# SOC_Power_Pins.net
KiCad netlist of a schematic drawn in Altium Designer
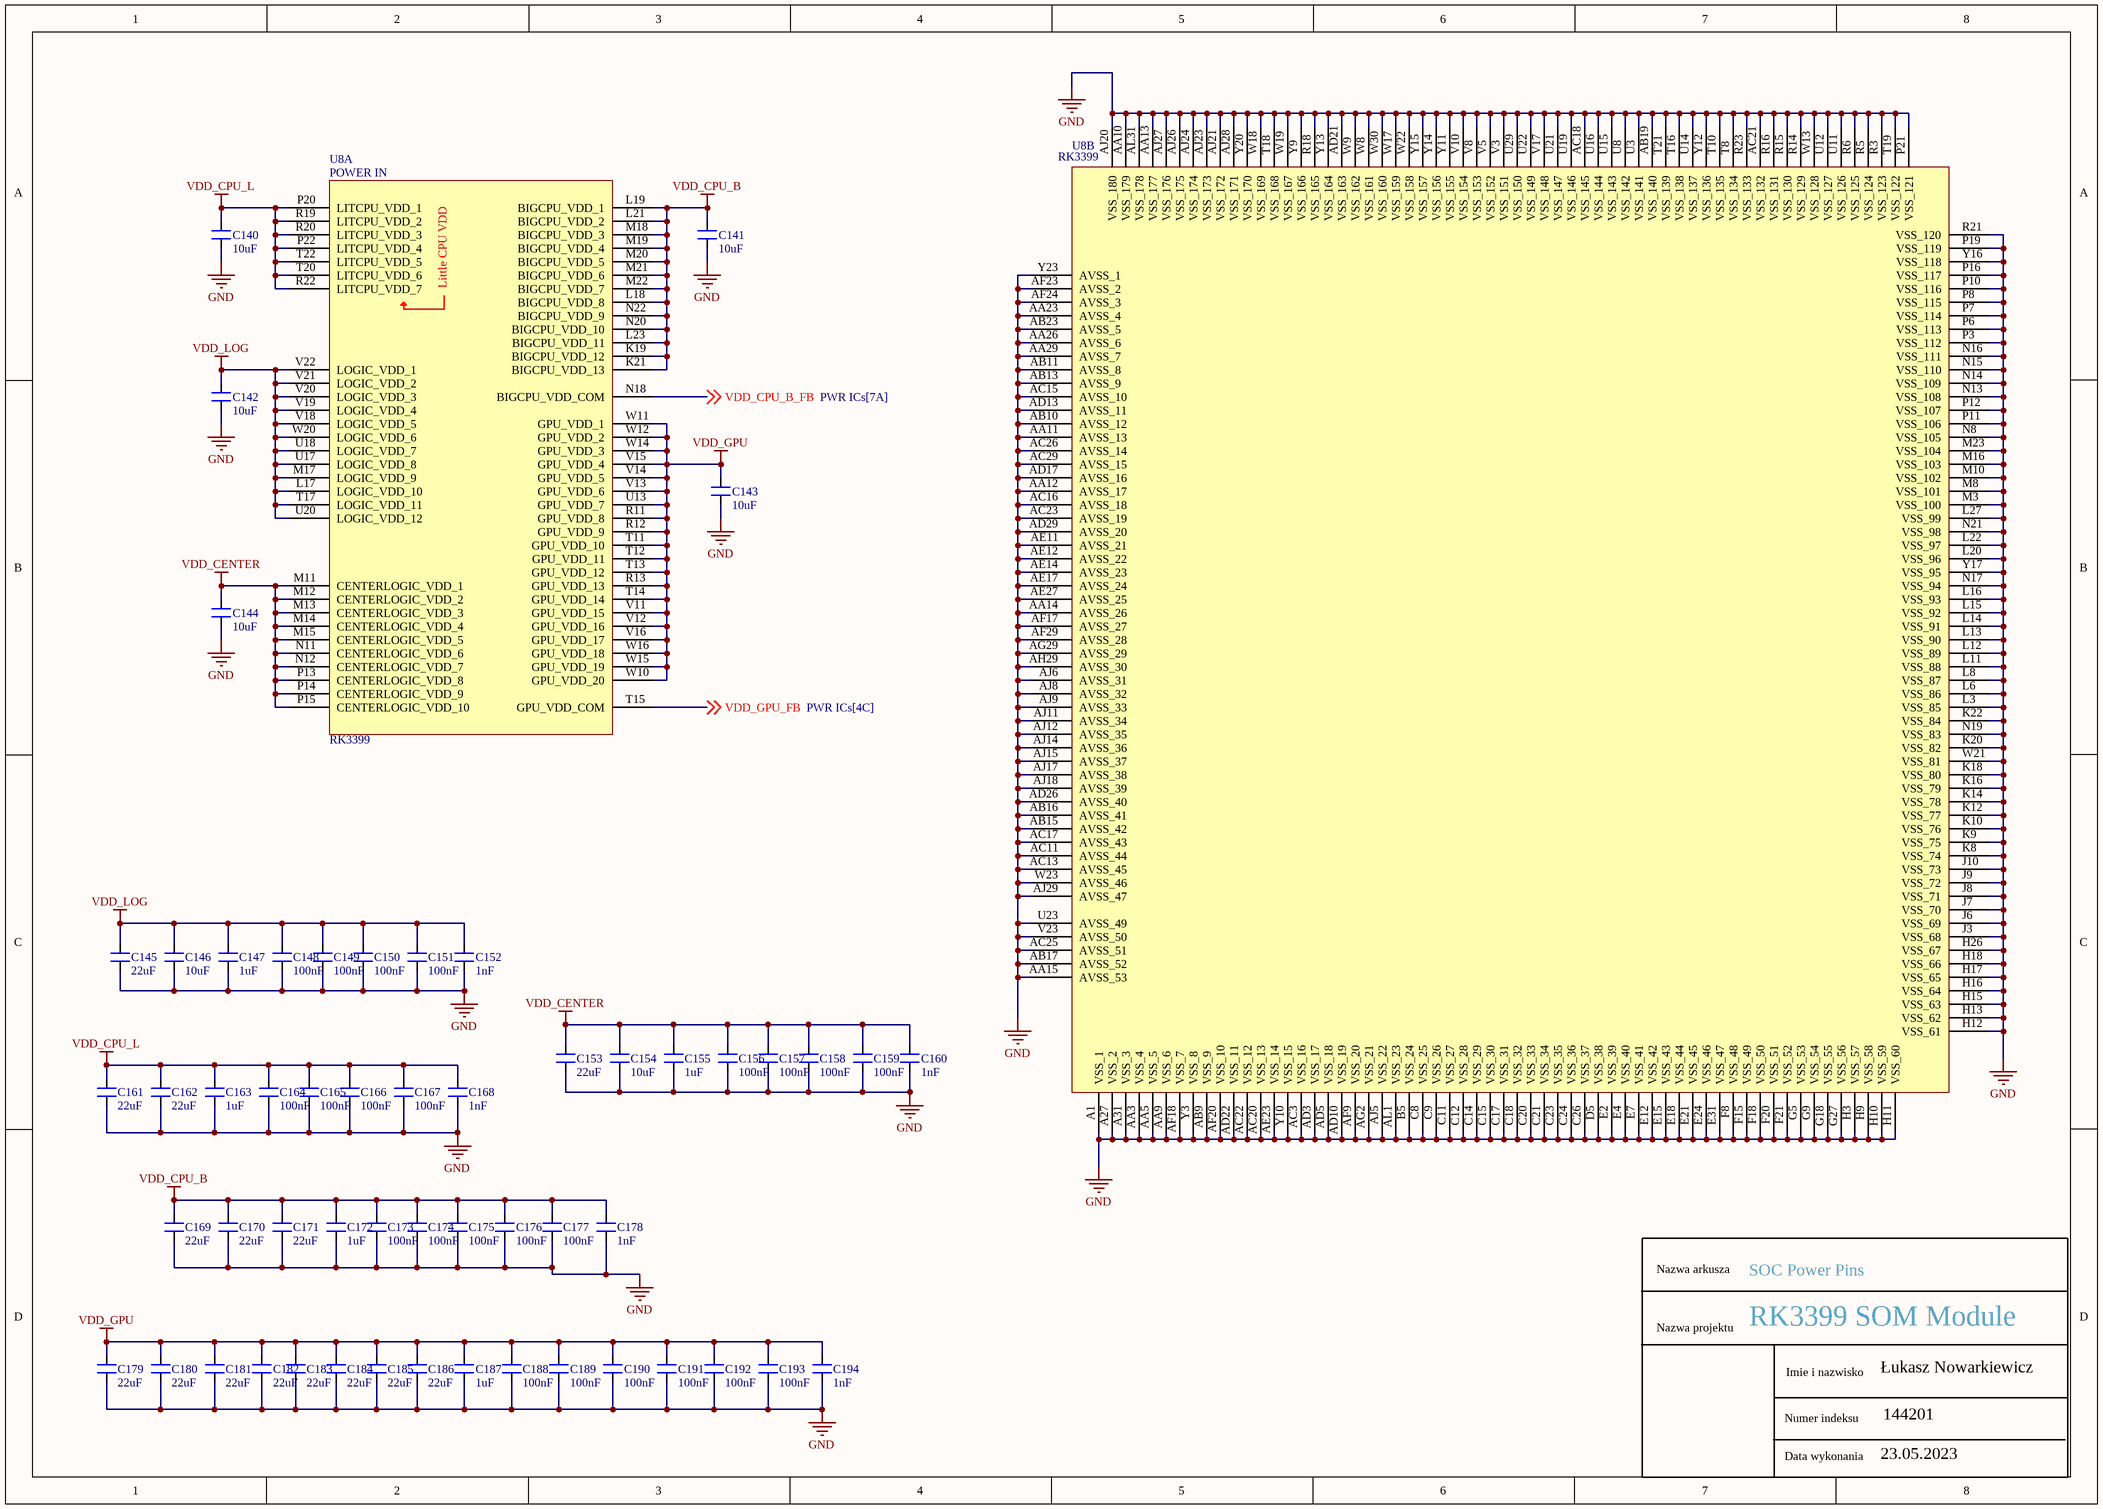
[diagram p0: SOC Power Pins.SchDoc]

(export (version "E")
  (design (tool "Eeschema 10.0.6"))
  (components
    (comp (ref "C140")
      (value "10uF")
      (footprint "CAP_0402")
      (description "10µF ±20% 10V Ceramic Capacitor X5R 0402 (1005 Metric)")
      (fields
        (field (name "MANUFACTURER PART NUMBER") "CL05A106MP5NUNC")
        (field (name "MANUFACTURER") "Samsung Electro-Mechanics")
      )
      (libsource (lib "RK3399 _Module_Schlib") (part "CAP_10uF-10V-20%-0402"))
    )
    (comp (ref "C141")
      (value "10uF")
      (footprint "CAP_0402")
      (description "10µF ±20% 10V Ceramic Capacitor X5R 0402 (1005 Metric)")
      (fields
        (field (name "MANUFACTURER PART NUMBER") "CL05A106MP5NUNC")
        (field (name "MANUFACTURER") "Samsung Electro-Mechanics")
      )
      (libsource (lib "RK3399 _Module_Schlib") (part "CAP_10uF-10V-20%-0402"))
    )
    (comp (ref "C142")
      (value "10uF")
      (footprint "CAP_0402")
      (description "10µF ±20% 10V Ceramic Capacitor X5R 0402 (1005 Metric)")
      (fields
        (field (name "MANUFACTURER PART NUMBER") "CL05A106MP5NUNC")
        (field (name "MANUFACTURER") "Samsung Electro-Mechanics")
      )
      (libsource (lib "RK3399 _Module_Schlib") (part "CAP_10uF-10V-20%-0402"))
    )
    (comp (ref "C143")
      (value "10uF")
      (footprint "CAP_0402")
      (description "10µF ±20% 10V Ceramic Capacitor X5R 0402 (1005 Metric)")
      (fields
        (field (name "MANUFACTURER PART NUMBER") "CL05A106MP5NUNC")
        (field (name "MANUFACTURER") "Samsung Electro-Mechanics")
      )
      (libsource (lib "RK3399 _Module_Schlib") (part "CAP_10uF-10V-20%-0402"))
    )
    (comp (ref "C144")
      (value "10uF")
      (footprint "CAP_0402")
      (description "10µF ±20% 10V Ceramic Capacitor X5R 0402 (1005 Metric)")
      (fields
        (field (name "MANUFACTURER PART NUMBER") "CL05A106MP5NUNC")
        (field (name "MANUFACTURER") "Samsung Electro-Mechanics")
      )
      (libsource (lib "RK3399 _Module_Schlib") (part "CAP_10uF-10V-20%-0402"))
    )
    (comp (ref "C145")
      (value "22uF")
      (footprint "CAP_0402")
      (description "22µF ±20% 6.3V Ceramic Capacitor X5R 0402 (1005 Metric)")
      (fields
        (field (name "MANUFACTURER") "Murata Electronics")
        (field (name "MANUFACTURER PART NUMBER") "CL05A226MQ5N6J8")
      )
      (libsource (lib "RK3399 _Module_Intlib") (part "CAP_22uF-6.3V-20%-0402"))
    )
    (comp (ref "C146")
      (value "10uF")
      (footprint "CAP_0402")
      (description "10µF ±20% 10V Ceramic Capacitor X5R 0402 (1005 Metric)")
      (fields
        (field (name "MANUFACTURER PART NUMBER") "CL05A106MP5NUNC")
        (field (name "MANUFACTURER") "Samsung Electro-Mechanics")
      )
      (libsource (lib "RK3399 _Module_Schlib") (part "CAP_10uF-10V-20%-0402"))
    )
    (comp (ref "C147")
      (value "1uF")
      (footprint "CAP_0201")
      (description "1µF ±20% 16V Ceramic Capacitor X5R 0201 (0603 Metric)")
      (fields
        (field (name "MANUFACTURER") "Samsung Electro-Mechanics")
        (field (name "MANUFACTURER PART NUMBER") "CL03A105MO3NRNH")
      )
      (libsource (lib "RK3399 _Module_Intlib") (part "CAP_1uF-16V-10%-0201"))
    )
    (comp (ref "C148")
      (value "100nF")
      (footprint "CAP_0201")
      (description "0.1µF ±10% 25V Ceramic Capacitor X5R 0201 (0603 Metric)")
      (fields
        (field (name "MANUFACTURER") "TDK Corporation")
        (field (name "MANUFACTURER PART NUMBER") "C0603X5R1E104K030BB")
      )
      (libsource (lib "RK3399 _Module_Intlib") (part "CAP_100nF-25V-10%-0201"))
    )
    (comp (ref "C149")
      (value "100nF")
      (footprint "CAP_0201")
      (description "0.1µF ±10% 25V Ceramic Capacitor X5R 0201 (0603 Metric)")
      (fields
        (field (name "MANUFACTURER") "TDK Corporation")
        (field (name "MANUFACTURER PART NUMBER") "C0603X5R1E104K030BB")
      )
      (libsource (lib "RK3399 _Module_Intlib") (part "CAP_100nF-25V-10%-0201"))
    )
    (comp (ref "C150")
      (value "100nF")
      (footprint "CAP_0201")
      (description "0.1µF ±10% 25V Ceramic Capacitor X5R 0201 (0603 Metric)")
      (fields
        (field (name "MANUFACTURER") "TDK Corporation")
        (field (name "MANUFACTURER PART NUMBER") "C0603X5R1E104K030BB")
      )
      (libsource (lib "RK3399 _Module_Intlib") (part "CAP_100nF-25V-10%-0201"))
    )
    (comp (ref "C151")
      (value "100nF")
      (footprint "CAP_0201")
      (description "0.1µF ±10% 25V Ceramic Capacitor X5R 0201 (0603 Metric)")
      (fields
        (field (name "MANUFACTURER") "TDK Corporation")
        (field (name "MANUFACTURER PART NUMBER") "C0603X5R1E104K030BB")
      )
      (libsource (lib "RK3399 _Module_Intlib") (part "CAP_100nF-25V-10%-0201"))
    )
    (comp (ref "C152")
      (value "1nF")
      (footprint "CAP_0201")
      (description "1000pF ±10% 16V Ceramic Capacitor X7R 0201 (0603 Metric)")
      (fields
        (field (name "MANUFACTURER") "Murata Electronics")
        (field (name "MANUFACTURER PART NUMBER") "GRM033R71C102KA01D")
      )
      (libsource (lib "RK3399 _Module_Intlib") (part "CAP_1nF-16V-10%-0201"))
    )
    (comp (ref "C153")
      (value "22uF")
      (footprint "CAP_0402")
      (description "22µF ±20% 6.3V Ceramic Capacitor X5R 0402 (1005 Metric)")
      (fields
        (field (name "MANUFACTURER") "Murata Electronics")
        (field (name "MANUFACTURER PART NUMBER") "CL05A226MQ5N6J8")
      )
      (libsource (lib "RK3399 _Module_Intlib") (part "CAP_22uF-6.3V-20%-0402"))
    )
    (comp (ref "C154")
      (value "10uF")
      (footprint "CAP_0402")
      (description "10µF ±20% 10V Ceramic Capacitor X5R 0402 (1005 Metric)")
      (fields
        (field (name "MANUFACTURER PART NUMBER") "CL05A106MP5NUNC")
        (field (name "MANUFACTURER") "Samsung Electro-Mechanics")
      )
      (libsource (lib "RK3399 _Module_Schlib") (part "CAP_10uF-10V-20%-0402"))
    )
    (comp (ref "C155")
      (value "1uF")
      (footprint "CAP_0201")
      (description "1µF ±20% 16V Ceramic Capacitor X5R 0201 (0603 Metric)")
      (fields
        (field (name "MANUFACTURER") "Samsung Electro-Mechanics")
        (field (name "MANUFACTURER PART NUMBER") "CL03A105MO3NRNH")
      )
      (libsource (lib "RK3399 _Module_Intlib") (part "CAP_1uF-16V-10%-0201"))
    )
    (comp (ref "C156")
      (value "100nF")
      (footprint "CAP_0201")
      (description "0.1µF ±10% 25V Ceramic Capacitor X5R 0201 (0603 Metric)")
      (fields
        (field (name "MANUFACTURER") "TDK Corporation")
        (field (name "MANUFACTURER PART NUMBER") "C0603X5R1E104K030BB")
      )
      (libsource (lib "RK3399 _Module_Intlib") (part "CAP_100nF-25V-10%-0201"))
    )
    (comp (ref "C157")
      (value "100nF")
      (footprint "CAP_0201")
      (description "0.1µF ±10% 25V Ceramic Capacitor X5R 0201 (0603 Metric)")
      (fields
        (field (name "MANUFACTURER") "TDK Corporation")
        (field (name "MANUFACTURER PART NUMBER") "C0603X5R1E104K030BB")
      )
      (libsource (lib "RK3399 _Module_Intlib") (part "CAP_100nF-25V-10%-0201"))
    )
    (comp (ref "C158")
      (value "100nF")
      (footprint "CAP_0201")
      (description "0.1µF ±10% 25V Ceramic Capacitor X5R 0201 (0603 Metric)")
      (fields
        (field (name "MANUFACTURER") "TDK Corporation")
        (field (name "MANUFACTURER PART NUMBER") "C0603X5R1E104K030BB")
      )
      (libsource (lib "RK3399 _Module_Intlib") (part "CAP_100nF-25V-10%-0201"))
    )
    (comp (ref "C159")
      (value "100nF")
      (footprint "CAP_0201")
      (description "0.1µF ±10% 25V Ceramic Capacitor X5R 0201 (0603 Metric)")
      (fields
        (field (name "MANUFACTURER") "TDK Corporation")
        (field (name "MANUFACTURER PART NUMBER") "C0603X5R1E104K030BB")
      )
      (libsource (lib "RK3399 _Module_Intlib") (part "CAP_100nF-25V-10%-0201"))
    )
    (comp (ref "C160")
      (value "1nF")
      (footprint "CAP_0201")
      (description "1000pF ±10% 16V Ceramic Capacitor X7R 0201 (0603 Metric)")
      (fields
        (field (name "MANUFACTURER") "Murata Electronics")
        (field (name "MANUFACTURER PART NUMBER") "GRM033R71C102KA01D")
      )
      (libsource (lib "RK3399 _Module_Intlib") (part "CAP_1nF-16V-10%-0201"))
    )
    (comp (ref "C161")
      (value "22uF")
      (footprint "CAP_0402")
      (description "22µF ±20% 6.3V Ceramic Capacitor X5R 0402 (1005 Metric)")
      (fields
        (field (name "MANUFACTURER") "Murata Electronics")
        (field (name "MANUFACTURER PART NUMBER") "CL05A226MQ5N6J8")
      )
      (libsource (lib "RK3399 _Module_Intlib") (part "CAP_22uF-6.3V-20%-0402"))
    )
    (comp (ref "C162")
      (value "22uF")
      (footprint "CAP_0402")
      (description "22µF ±20% 6.3V Ceramic Capacitor X5R 0402 (1005 Metric)")
      (fields
        (field (name "MANUFACTURER") "Murata Electronics")
        (field (name "MANUFACTURER PART NUMBER") "CL05A226MQ5N6J8")
      )
      (libsource (lib "RK3399 _Module_Intlib") (part "CAP_22uF-6.3V-20%-0402"))
    )
    (comp (ref "C163")
      (value "1uF")
      (footprint "CAP_0201")
      (description "1µF ±20% 16V Ceramic Capacitor X5R 0201 (0603 Metric)")
      (fields
        (field (name "MANUFACTURER") "Samsung Electro-Mechanics")
        (field (name "MANUFACTURER PART NUMBER") "CL03A105MO3NRNH")
      )
      (libsource (lib "RK3399 _Module_Intlib") (part "CAP_1uF-16V-10%-0201"))
    )
    (comp (ref "C164")
      (value "100nF")
      (footprint "CAP_0201")
      (description "0.1µF ±10% 25V Ceramic Capacitor X5R 0201 (0603 Metric)")
      (fields
        (field (name "MANUFACTURER") "TDK Corporation")
        (field (name "MANUFACTURER PART NUMBER") "C0603X5R1E104K030BB")
      )
      (libsource (lib "RK3399 _Module_Intlib") (part "CAP_100nF-25V-10%-0201"))
    )
    (comp (ref "C165")
      (value "100nF")
      (footprint "CAP_0201")
      (description "0.1µF ±10% 25V Ceramic Capacitor X5R 0201 (0603 Metric)")
      (fields
        (field (name "MANUFACTURER") "TDK Corporation")
        (field (name "MANUFACTURER PART NUMBER") "C0603X5R1E104K030BB")
      )
      (libsource (lib "RK3399 _Module_Intlib") (part "CAP_100nF-25V-10%-0201"))
    )
    (comp (ref "C166")
      (value "100nF")
      (footprint "CAP_0201")
      (description "0.1µF ±10% 25V Ceramic Capacitor X5R 0201 (0603 Metric)")
      (fields
        (field (name "MANUFACTURER") "TDK Corporation")
        (field (name "MANUFACTURER PART NUMBER") "C0603X5R1E104K030BB")
      )
      (libsource (lib "RK3399 _Module_Intlib") (part "CAP_100nF-25V-10%-0201"))
    )
    (comp (ref "C167")
      (value "100nF")
      (footprint "CAP_0201")
      (description "0.1µF ±10% 25V Ceramic Capacitor X5R 0201 (0603 Metric)")
      (fields
        (field (name "MANUFACTURER") "TDK Corporation")
        (field (name "MANUFACTURER PART NUMBER") "C0603X5R1E104K030BB")
      )
      (libsource (lib "RK3399 _Module_Intlib") (part "CAP_100nF-25V-10%-0201"))
    )
    (comp (ref "C168")
      (value "1nF")
      (footprint "CAP_0201")
      (description "1000pF ±10% 16V Ceramic Capacitor X7R 0201 (0603 Metric)")
      (fields
        (field (name "MANUFACTURER") "Murata Electronics")
        (field (name "MANUFACTURER PART NUMBER") "GRM033R71C102KA01D")
      )
      (libsource (lib "RK3399 _Module_Intlib") (part "CAP_1nF-16V-10%-0201"))
    )
    (comp (ref "C169")
      (value "22uF")
      (footprint "CAP_0402")
      (description "22µF ±20% 6.3V Ceramic Capacitor X5R 0402 (1005 Metric)")
      (fields
        (field (name "MANUFACTURER") "Murata Electronics")
        (field (name "MANUFACTURER PART NUMBER") "CL05A226MQ5N6J8")
      )
      (libsource (lib "RK3399 _Module_Intlib") (part "CAP_22uF-6.3V-20%-0402"))
    )
    (comp (ref "C170")
      (value "22uF")
      (footprint "CAP_0402")
      (description "22µF ±20% 6.3V Ceramic Capacitor X5R 0402 (1005 Metric)")
      (fields
        (field (name "MANUFACTURER") "Murata Electronics")
        (field (name "MANUFACTURER PART NUMBER") "CL05A226MQ5N6J8")
      )
      (libsource (lib "RK3399 _Module_Intlib") (part "CAP_22uF-6.3V-20%-0402"))
    )
    (comp (ref "C171")
      (value "22uF")
      (footprint "CAP_0402")
      (description "22µF ±20% 6.3V Ceramic Capacitor X5R 0402 (1005 Metric)")
      (fields
        (field (name "MANUFACTURER") "Murata Electronics")
        (field (name "MANUFACTURER PART NUMBER") "CL05A226MQ5N6J8")
      )
      (libsource (lib "RK3399 _Module_Intlib") (part "CAP_22uF-6.3V-20%-0402"))
    )
    (comp (ref "C172")
      (value "1uF")
      (footprint "CAP_0201")
      (description "1µF ±20% 16V Ceramic Capacitor X5R 0201 (0603 Metric)")
      (fields
        (field (name "MANUFACTURER") "Samsung Electro-Mechanics")
        (field (name "MANUFACTURER PART NUMBER") "CL03A105MO3NRNH")
      )
      (libsource (lib "RK3399 _Module_Intlib") (part "CAP_1uF-16V-10%-0201"))
    )
    (comp (ref "C173")
      (value "100nF")
      (footprint "CAP_0201")
      (description "0.1µF ±10% 25V Ceramic Capacitor X5R 0201 (0603 Metric)")
      (fields
        (field (name "MANUFACTURER") "TDK Corporation")
        (field (name "MANUFACTURER PART NUMBER") "C0603X5R1E104K030BB")
      )
      (libsource (lib "RK3399 _Module_Intlib") (part "CAP_100nF-25V-10%-0201"))
    )
    (comp (ref "C174")
      (value "100nF")
      (footprint "CAP_0201")
      (description "0.1µF ±10% 25V Ceramic Capacitor X5R 0201 (0603 Metric)")
      (fields
        (field (name "MANUFACTURER") "TDK Corporation")
        (field (name "MANUFACTURER PART NUMBER") "C0603X5R1E104K030BB")
      )
      (libsource (lib "RK3399 _Module_Intlib") (part "CAP_100nF-25V-10%-0201"))
    )
    (comp (ref "C175")
      (value "100nF")
      (footprint "CAP_0201")
      (description "0.1µF ±10% 25V Ceramic Capacitor X5R 0201 (0603 Metric)")
      (fields
        (field (name "MANUFACTURER") "TDK Corporation")
        (field (name "MANUFACTURER PART NUMBER") "C0603X5R1E104K030BB")
      )
      (libsource (lib "RK3399 _Module_Intlib") (part "CAP_100nF-25V-10%-0201"))
    )
    (comp (ref "C176")
      (value "100nF")
      (footprint "CAP_0201")
      (description "0.1µF ±10% 25V Ceramic Capacitor X5R 0201 (0603 Metric)")
      (fields
        (field (name "MANUFACTURER") "TDK Corporation")
        (field (name "MANUFACTURER PART NUMBER") "C0603X5R1E104K030BB")
      )
      (libsource (lib "RK3399 _Module_Intlib") (part "CAP_100nF-25V-10%-0201"))
    )
    (comp (ref "C177")
      (value "100nF")
      (footprint "CAP_0201")
      (description "0.1µF ±10% 25V Ceramic Capacitor X5R 0201 (0603 Metric)")
      (fields
        (field (name "MANUFACTURER") "TDK Corporation")
        (field (name "MANUFACTURER PART NUMBER") "C0603X5R1E104K030BB")
      )
      (libsource (lib "RK3399 _Module_Intlib") (part "CAP_100nF-25V-10%-0201"))
    )
    (comp (ref "C178")
      (value "1nF")
      (footprint "CAP_0201")
      (description "1000pF ±10% 16V Ceramic Capacitor X7R 0201 (0603 Metric)")
      (fields
        (field (name "MANUFACTURER") "Murata Electronics")
        (field (name "MANUFACTURER PART NUMBER") "GRM033R71C102KA01D")
      )
      (libsource (lib "RK3399 _Module_Intlib") (part "CAP_1nF-16V-10%-0201"))
    )
    (comp (ref "C179")
      (value "22uF")
      (footprint "CAP_0402")
      (description "22µF ±20% 6.3V Ceramic Capacitor X5R 0402 (1005 Metric)")
      (fields
        (field (name "MANUFACTURER") "Murata Electronics")
        (field (name "MANUFACTURER PART NUMBER") "CL05A226MQ5N6J8")
      )
      (libsource (lib "RK3399 _Module_Intlib") (part "CAP_22uF-6.3V-20%-0402"))
    )
    (comp (ref "C180")
      (value "22uF")
      (footprint "CAP_0402")
      (description "22µF ±20% 6.3V Ceramic Capacitor X5R 0402 (1005 Metric)")
      (fields
        (field (name "MANUFACTURER") "Murata Electronics")
        (field (name "MANUFACTURER PART NUMBER") "CL05A226MQ5N6J8")
      )
      (libsource (lib "RK3399 _Module_Intlib") (part "CAP_22uF-6.3V-20%-0402"))
    )
    (comp (ref "C181")
      (value "22uF")
      (footprint "CAP_0402")
      (description "22µF ±20% 6.3V Ceramic Capacitor X5R 0402 (1005 Metric)")
      (fields
        (field (name "MANUFACTURER") "Murata Electronics")
        (field (name "MANUFACTURER PART NUMBER") "CL05A226MQ5N6J8")
      )
      (libsource (lib "RK3399 _Module_Intlib") (part "CAP_22uF-6.3V-20%-0402"))
    )
    (comp (ref "C182")
      (value "22uF")
      (footprint "CAP_0402")
      (description "22µF ±20% 6.3V Ceramic Capacitor X5R 0402 (1005 Metric)")
      (fields
        (field (name "MANUFACTURER") "Murata Electronics")
        (field (name "MANUFACTURER PART NUMBER") "CL05A226MQ5N6J8")
      )
      (libsource (lib "RK3399 _Module_Intlib") (part "CAP_22uF-6.3V-20%-0402"))
    )
    (comp (ref "C183")
      (value "22uF")
      (footprint "CAP_0402")
      (description "22µF ±20% 6.3V Ceramic Capacitor X5R 0402 (1005 Metric)")
      (fields
        (field (name "MANUFACTURER") "Murata Electronics")
        (field (name "MANUFACTURER PART NUMBER") "CL05A226MQ5N6J8")
      )
      (libsource (lib "RK3399 _Module_Intlib") (part "CAP_22uF-6.3V-20%-0402"))
    )
    (comp (ref "C184")
      (value "22uF")
      (footprint "CAP_0402")
      (description "22µF ±20% 6.3V Ceramic Capacitor X5R 0402 (1005 Metric)")
      (fields
        (field (name "MANUFACTURER") "Murata Electronics")
        (field (name "MANUFACTURER PART NUMBER") "CL05A226MQ5N6J8")
      )
      (libsource (lib "RK3399 _Module_Intlib") (part "CAP_22uF-6.3V-20%-0402"))
    )
    (comp (ref "C185")
      (value "22uF")
      (footprint "CAP_0402")
      (description "22µF ±20% 6.3V Ceramic Capacitor X5R 0402 (1005 Metric)")
      (fields
        (field (name "MANUFACTURER") "Murata Electronics")
        (field (name "MANUFACTURER PART NUMBER") "CL05A226MQ5N6J8")
      )
      (libsource (lib "RK3399 _Module_Intlib") (part "CAP_22uF-6.3V-20%-0402"))
    )
    (comp (ref "C186")
      (value "22uF")
      (footprint "CAP_0402")
      (description "22µF ±20% 6.3V Ceramic Capacitor X5R 0402 (1005 Metric)")
      (fields
        (field (name "MANUFACTURER") "Murata Electronics")
        (field (name "MANUFACTURER PART NUMBER") "CL05A226MQ5N6J8")
      )
      (libsource (lib "RK3399 _Module_Intlib") (part "CAP_22uF-6.3V-20%-0402"))
    )
    (comp (ref "C187")
      (value "1uF")
      (footprint "CAP_0201")
      (description "1µF ±20% 16V Ceramic Capacitor X5R 0201 (0603 Metric)")
      (fields
        (field (name "MANUFACTURER") "Samsung Electro-Mechanics")
        (field (name "MANUFACTURER PART NUMBER") "CL03A105MO3NRNH")
      )
      (libsource (lib "RK3399 _Module_Intlib") (part "CAP_1uF-16V-10%-0201"))
    )
    (comp (ref "C188")
      (value "100nF")
      (footprint "CAP_0201")
      (description "0.1µF ±10% 25V Ceramic Capacitor X5R 0201 (0603 Metric)")
      (fields
        (field (name "MANUFACTURER") "TDK Corporation")
        (field (name "MANUFACTURER PART NUMBER") "C0603X5R1E104K030BB")
      )
      (libsource (lib "RK3399 _Module_Intlib") (part "CAP_100nF-25V-10%-0201"))
    )
    (comp (ref "C189")
      (value "100nF")
      (footprint "CAP_0201")
      (description "0.1µF ±10% 25V Ceramic Capacitor X5R 0201 (0603 Metric)")
      (fields
        (field (name "MANUFACTURER") "TDK Corporation")
        (field (name "MANUFACTURER PART NUMBER") "C0603X5R1E104K030BB")
      )
      (libsource (lib "RK3399 _Module_Intlib") (part "CAP_100nF-25V-10%-0201"))
    )
    (comp (ref "C190")
      (value "100nF")
      (footprint "CAP_0201")
      (description "0.1µF ±10% 25V Ceramic Capacitor X5R 0201 (0603 Metric)")
      (fields
        (field (name "MANUFACTURER") "TDK Corporation")
        (field (name "MANUFACTURER PART NUMBER") "C0603X5R1E104K030BB")
      )
      (libsource (lib "RK3399 _Module_Intlib") (part "CAP_100nF-25V-10%-0201"))
    )
    (comp (ref "C191")
      (value "100nF")
      (footprint "CAP_0201")
      (description "0.1µF ±10% 25V Ceramic Capacitor X5R 0201 (0603 Metric)")
      (fields
        (field (name "MANUFACTURER") "TDK Corporation")
        (field (name "MANUFACTURER PART NUMBER") "C0603X5R1E104K030BB")
      )
      (libsource (lib "RK3399 _Module_Intlib") (part "CAP_100nF-25V-10%-0201"))
    )
    (comp (ref "C192")
      (value "100nF")
      (footprint "CAP_0201")
      (description "0.1µF ±10% 25V Ceramic Capacitor X5R 0201 (0603 Metric)")
      (fields
        (field (name "MANUFACTURER") "TDK Corporation")
        (field (name "MANUFACTURER PART NUMBER") "C0603X5R1E104K030BB")
      )
      (libsource (lib "RK3399 _Module_Intlib") (part "CAP_100nF-25V-10%-0201"))
    )
    (comp (ref "C193")
      (value "100nF")
      (footprint "CAP_0201")
      (description "0.1µF ±10% 25V Ceramic Capacitor X5R 0201 (0603 Metric)")
      (fields
        (field (name "MANUFACTURER") "TDK Corporation")
        (field (name "MANUFACTURER PART NUMBER") "C0603X5R1E104K030BB")
      )
      (libsource (lib "RK3399 _Module_Intlib") (part "CAP_100nF-25V-10%-0201"))
    )
    (comp (ref "C194")
      (value "1nF")
      (footprint "CAP_0201")
      (description "1000pF ±10% 16V Ceramic Capacitor X7R 0201 (0603 Metric)")
      (fields
        (field (name "MANUFACTURER") "Murata Electronics")
        (field (name "MANUFACTURER PART NUMBER") "GRM033R71C102KA01D")
      )
      (libsource (lib "RK3399 _Module_Intlib") (part "CAP_1nF-16V-10%-0201"))
    )
    (comp (ref "U8")
      (value "RK3399")
      (footprint "FBGA828_23_826X826")
      (description "RK3399 is a low power, high performance processor for computing, personal mobile.")
      (fields (field (name "MANUFACTURER") "Rockchip"))
      (libsource (lib "EsteemPCB_SOM_Course_intlib") (part "IC_RK3399-FCBGA828"))
    )
  )
  (nets
    (net (code "1") (name "GND") (class "Default")
      (node (ref "C140") (pin "1") (pinfunction "1_1") (pintype "passive"))
      (node (ref "C141") (pin "1") (pinfunction "1_1") (pintype "passive"))
      (node (ref "C142") (pin "1") (pinfunction "1_1") (pintype "passive"))
      (node (ref "C143") (pin "1") (pinfunction "1_1") (pintype "passive"))
      (node (ref "C144") (pin "1") (pinfunction "1_1") (pintype "passive"))
      (node (ref "C145") (pin "1") (pinfunction "1_1") (pintype "passive"))
      (node (ref "C146") (pin "1") (pinfunction "1_1") (pintype "passive"))
      (node (ref "C147") (pin "1") (pinfunction "1_1") (pintype "passive"))
      (node (ref "C148") (pin "1") (pinfunction "1_1") (pintype "passive"))
      (node (ref "C149") (pin "1") (pinfunction "1_1") (pintype "passive"))
      (node (ref "C150") (pin "1") (pinfunction "1_1") (pintype "passive"))
      (node (ref "C151") (pin "1") (pinfunction "1_1") (pintype "passive"))
      (node (ref "C152") (pin "1") (pinfunction "1_1") (pintype "passive"))
      (node (ref "C153") (pin "1") (pinfunction "1_1") (pintype "passive"))
      (node (ref "C154") (pin "1") (pinfunction "1_1") (pintype "passive"))
      (node (ref "C155") (pin "1") (pinfunction "1_1") (pintype "passive"))
      (node (ref "C156") (pin "1") (pinfunction "1_1") (pintype "passive"))
      (node (ref "C157") (pin "1") (pinfunction "1_1") (pintype "passive"))
      (node (ref "C158") (pin "1") (pinfunction "1_1") (pintype "passive"))
      (node (ref "C159") (pin "1") (pinfunction "1_1") (pintype "passive"))
      (node (ref "C160") (pin "1") (pinfunction "1_1") (pintype "passive"))
      (node (ref "C161") (pin "1") (pinfunction "1_1") (pintype "passive"))
      (node (ref "C162") (pin "1") (pinfunction "1_1") (pintype "passive"))
      (node (ref "C163") (pin "1") (pinfunction "1_1") (pintype "passive"))
      (node (ref "C164") (pin "1") (pinfunction "1_1") (pintype "passive"))
      (node (ref "C165") (pin "1") (pinfunction "1_1") (pintype "passive"))
      (node (ref "C166") (pin "1") (pinfunction "1_1") (pintype "passive"))
      (node (ref "C167") (pin "1") (pinfunction "1_1") (pintype "passive"))
      (node (ref "C168") (pin "1") (pinfunction "1_1") (pintype "passive"))
      (node (ref "C169") (pin "1") (pinfunction "1_1") (pintype "passive"))
      (node (ref "C170") (pin "1") (pinfunction "1_1") (pintype "passive"))
      (node (ref "C171") (pin "1") (pinfunction "1_1") (pintype "passive"))
      (node (ref "C172") (pin "1") (pinfunction "1_1") (pintype "passive"))
      (node (ref "C173") (pin "1") (pinfunction "1_1") (pintype "passive"))
      (node (ref "C174") (pin "1") (pinfunction "1_1") (pintype "passive"))
      (node (ref "C175") (pin "1") (pinfunction "1_1") (pintype "passive"))
      (node (ref "C176") (pin "1") (pinfunction "1_1") (pintype "passive"))
      (node (ref "C177") (pin "1") (pinfunction "1_1") (pintype "passive"))
      (node (ref "C178") (pin "1") (pinfunction "1_1") (pintype "passive"))
      (node (ref "C179") (pin "1") (pinfunction "1_1") (pintype "passive"))
      (node (ref "C180") (pin "1") (pinfunction "1_1") (pintype "passive"))
      (node (ref "C181") (pin "1") (pinfunction "1_1") (pintype "passive"))
      (node (ref "C182") (pin "1") (pinfunction "1_1") (pintype "passive"))
      (node (ref "C183") (pin "1") (pinfunction "1_1") (pintype "passive"))
      (node (ref "C184") (pin "1") (pinfunction "1_1") (pintype "passive"))
      (node (ref "C185") (pin "1") (pinfunction "1_1") (pintype "passive"))
      (node (ref "C186") (pin "1") (pinfunction "1_1") (pintype "passive"))
      (node (ref "C187") (pin "1") (pinfunction "1_1") (pintype "passive"))
      (node (ref "C188") (pin "1") (pinfunction "1_1") (pintype "passive"))
      (node (ref "C189") (pin "1") (pinfunction "1_1") (pintype "passive"))
      (node (ref "C190") (pin "1") (pinfunction "1_1") (pintype "passive"))
      (node (ref "C191") (pin "1") (pinfunction "1_1") (pintype "passive"))
      (node (ref "C192") (pin "1") (pinfunction "1_1") (pintype "passive"))
      (node (ref "C193") (pin "1") (pinfunction "1_1") (pintype "passive"))
      (node (ref "C194") (pin "1") (pinfunction "1_1") (pintype "passive"))
      (node (ref "U8") (pin "A1") (pinfunction "VSS_1_A1") (pintype "passive"))
      (node (ref "U8") (pin "A27") (pinfunction "VSS_2_A27") (pintype "passive"))
      (node (ref "U8") (pin "A31") (pinfunction "VSS_3_A31") (pintype "passive"))
      (node (ref "U8") (pin "AA10") (pinfunction "VSS_179_AA10") (pintype "passive"))
      (node (ref "U8") (pin "AA11") (pinfunction "AVSS_13_AA11") (pintype "passive"))
      (node (ref "U8") (pin "AA12") (pinfunction "AVSS_17_AA12") (pintype "passive"))
      (node (ref "U8") (pin "AA13") (pinfunction "VSS_177_AA13") (pintype "passive"))
      (node (ref "U8") (pin "AA14") (pinfunction "AVSS_26_AA14") (pintype "passive"))
      (node (ref "U8") (pin "AA15") (pinfunction "AVSS_53_AA15") (pintype "passive"))
      (node (ref "U8") (pin "AA23") (pinfunction "AVSS_4_AA23") (pintype "passive"))
      (node (ref "U8") (pin "AA26") (pinfunction "AVSS_6_AA26") (pintype "passive"))
      (node (ref "U8") (pin "AA29") (pinfunction "AVSS_7_AA29") (pintype "passive"))
      (node (ref "U8") (pin "AA3") (pinfunction "VSS_4_AA3") (pintype "passive"))
      (node (ref "U8") (pin "AA5") (pinfunction "VSS_5_AA5") (pintype "passive"))
      (node (ref "U8") (pin "AA9") (pinfunction "VSS_6_AA9") (pintype "passive"))
      (node (ref "U8") (pin "AB10") (pinfunction "AVSS_12_AB10") (pintype "passive"))
      (node (ref "U8") (pin "AB11") (pinfunction "AVSS_8_AB11") (pintype "passive"))
      (node (ref "U8") (pin "AB13") (pinfunction "AVSS_9_AB13") (pintype "passive"))
      (node (ref "U8") (pin "AB15") (pinfunction "AVSS_42_AB15") (pintype "passive"))
      (node (ref "U8") (pin "AB16") (pinfunction "AVSS_41_AB16") (pintype "passive"))
      (node (ref "U8") (pin "AB17") (pinfunction "AVSS_52_AB17") (pintype "passive"))
      (node (ref "U8") (pin "AB19") (pinfunction "VSS_140_AB19") (pintype "passive"))
      (node (ref "U8") (pin "AB23") (pinfunction "AVSS_5_AB23") (pintype "passive"))
      (node (ref "U8") (pin "AB9") (pinfunction "VSS_9_AB9") (pintype "passive"))
      (node (ref "U8") (pin "AC11") (pinfunction "AVSS_44_AC11") (pintype "passive"))
      (node (ref "U8") (pin "AC13") (pinfunction "AVSS_45_AC13") (pintype "passive"))
      (node (ref "U8") (pin "AC15") (pinfunction "AVSS_10_AC15") (pintype "passive"))
      (node (ref "U8") (pin "AC16") (pinfunction "AVSS_18_AC16") (pintype "passive"))
      (node (ref "U8") (pin "AC17") (pinfunction "AVSS_43_AC17") (pintype "passive"))
      (node (ref "U8") (pin "AC18") (pinfunction "VSS_145_AC18") (pintype "passive"))
      (node (ref "U8") (pin "AC20") (pinfunction "VSS_13_AC20") (pintype "passive"))
      (node (ref "U8") (pin "AC21") (pinfunction "VSS_132_AC21") (pintype "passive"))
      (node (ref "U8") (pin "AC22") (pinfunction "VSS_12_AC22") (pintype "passive"))
      (node (ref "U8") (pin "AC23") (pinfunction "AVSS_19_AC23") (pintype "passive"))
      (node (ref "U8") (pin "AC25") (pinfunction "AVSS_51_AC25") (pintype "passive"))
      (node (ref "U8") (pin "AC26") (pinfunction "AVSS_14_AC26") (pintype "passive"))
      (node (ref "U8") (pin "AC29") (pinfunction "AVSS_15_AC29") (pintype "passive"))
      (node (ref "U8") (pin "AC3") (pinfunction "VSS_16_AC3") (pintype "passive"))
      (node (ref "U8") (pin "AD10") (pinfunction "VSS_19_AD10") (pintype "passive"))
      (node (ref "U8") (pin "AD13") (pinfunction "AVSS_11_AD13") (pintype "passive"))
      (node (ref "U8") (pin "AD17") (pinfunction "AVSS_16_AD17") (pintype "passive"))
      (node (ref "U8") (pin "AD21") (pinfunction "VSS_163_AD21") (pintype "passive"))
      (node (ref "U8") (pin "AD22") (pinfunction "VSS_11_AD22") (pintype "passive"))
      (node (ref "U8") (pin "AD26") (pinfunction "AVSS_40_AD26") (pintype "passive"))
      (node (ref "U8") (pin "AD29") (pinfunction "AVSS_20_AD29") (pintype "passive"))
      (node (ref "U8") (pin "AD3") (pinfunction "VSS_17_AD3") (pintype "passive"))
      (node (ref "U8") (pin "AD5") (pinfunction "VSS_18_AD5") (pintype "passive"))
      (node (ref "U8") (pin "AE11") (pinfunction "AVSS_21_AE11") (pintype "passive"))
      (node (ref "U8") (pin "AE12") (pinfunction "AVSS_22_AE12") (pintype "passive"))
      (node (ref "U8") (pin "AE14") (pinfunction "AVSS_23_AE14") (pintype "passive"))
      (node (ref "U8") (pin "AE17") (pinfunction "AVSS_24_AE17") (pintype "passive"))
      (node (ref "U8") (pin "AE23") (pinfunction "VSS_14_AE23") (pintype "passive"))
      (node (ref "U8") (pin "AE27") (pinfunction "AVSS_25_AE27") (pintype "passive"))
      (node (ref "U8") (pin "AF17") (pinfunction "AVSS_27_AF17") (pintype "passive"))
      (node (ref "U8") (pin "AF18") (pinfunction "VSS_7_AF18") (pintype "passive"))
      (node (ref "U8") (pin "AF20") (pinfunction "VSS_10_AF20") (pintype "passive"))
      (node (ref "U8") (pin "AF23") (pinfunction "AVSS_2_AF23") (pintype "passive"))
      (node (ref "U8") (pin "AF24") (pinfunction "AVSS_3_AF24") (pintype "passive"))
      (node (ref "U8") (pin "AF29") (pinfunction "AVSS_28_AF29") (pintype "passive"))
      (node (ref "U8") (pin "AF9") (pinfunction "VSS_20_AF9") (pintype "passive"))
      (node (ref "U8") (pin "AG2") (pinfunction "VSS_21_AG2") (pintype "passive"))
      (node (ref "U8") (pin "AG29") (pinfunction "AVSS_29_AG29") (pintype "passive"))
      (node (ref "U8") (pin "AH29") (pinfunction "AVSS_30_AH29") (pintype "passive"))
      (node (ref "U8") (pin "AJ11") (pinfunction "AVSS_34_AJ11") (pintype "passive"))
      (node (ref "U8") (pin "AJ12") (pinfunction "AVSS_35_AJ12") (pintype "passive"))
      (node (ref "U8") (pin "AJ14") (pinfunction "AVSS_36_AJ14") (pintype "passive"))
      (node (ref "U8") (pin "AJ15") (pinfunction "AVSS_37_AJ15") (pintype "passive"))
      (node (ref "U8") (pin "AJ17") (pinfunction "AVSS_38_AJ17") (pintype "passive"))
      (node (ref "U8") (pin "AJ18") (pinfunction "AVSS_39_AJ18") (pintype "passive"))
      (node (ref "U8") (pin "AJ20") (pinfunction "VSS_180_AJ20") (pintype "passive"))
      (node (ref "U8") (pin "AJ21") (pinfunction "VSS_172_AJ21") (pintype "passive"))
      (node (ref "U8") (pin "AJ23") (pinfunction "VSS_173_AJ23") (pintype "passive"))
      (node (ref "U8") (pin "AJ24") (pinfunction "VSS_174_AJ24") (pintype "passive"))
      (node (ref "U8") (pin "AJ26") (pinfunction "VSS_175_AJ26") (pintype "passive"))
      (node (ref "U8") (pin "AJ27") (pinfunction "VSS_176_AJ27") (pintype "passive"))
      (node (ref "U8") (pin "AJ28") (pinfunction "VSS_171_AJ28") (pintype "passive"))
      (node (ref "U8") (pin "AJ29") (pinfunction "AVSS_47_AJ29") (pintype "passive"))
      (node (ref "U8") (pin "AJ5") (pinfunction "VSS_22_AJ5") (pintype "passive"))
      (node (ref "U8") (pin "AJ6") (pinfunction "AVSS_31_AJ6") (pintype "passive"))
      (node (ref "U8") (pin "AJ8") (pinfunction "AVSS_32_AJ8") (pintype "passive"))
      (node (ref "U8") (pin "AJ9") (pinfunction "AVSS_33_AJ9") (pintype "passive"))
      (node (ref "U8") (pin "AL1") (pinfunction "VSS_23_AL1") (pintype "passive"))
      (node (ref "U8") (pin "AL31") (pinfunction "VSS_178_AL31") (pintype "passive"))
      (node (ref "U8") (pin "B5") (pinfunction "VSS_24_B5") (pintype "passive"))
      (node (ref "U8") (pin "C11") (pinfunction "VSS_27_C11") (pintype "passive"))
      (node (ref "U8") (pin "C12") (pinfunction "VSS_28_C12") (pintype "passive"))
      (node (ref "U8") (pin "C14") (pinfunction "VSS_29_C14") (pintype "passive"))
      (node (ref "U8") (pin "C15") (pinfunction "VSS_30_C15") (pintype "passive"))
      (node (ref "U8") (pin "C17") (pinfunction "VSS_31_C17") (pintype "passive"))
      (node (ref "U8") (pin "C18") (pinfunction "VSS_32_C18") (pintype "passive"))
      (node (ref "U8") (pin "C20") (pinfunction "VSS_33_C20") (pintype "passive"))
      (node (ref "U8") (pin "C21") (pinfunction "VSS_34_C21") (pintype "passive"))
      (node (ref "U8") (pin "C23") (pinfunction "VSS_35_C23") (pintype "passive"))
      (node (ref "U8") (pin "C24") (pinfunction "VSS_36_C24") (pintype "passive"))
      (node (ref "U8") (pin "C26") (pinfunction "VSS_37_C26") (pintype "passive"))
      (node (ref "U8") (pin "C8") (pinfunction "VSS_25_C8") (pintype "passive"))
      (node (ref "U8") (pin "C9") (pinfunction "VSS_26_C9") (pintype "passive"))
      (node (ref "U8") (pin "D5") (pinfunction "VSS_38_D5") (pintype "passive"))
      (node (ref "U8") (pin "E12") (pinfunction "VSS_42_E12") (pintype "passive"))
      (node (ref "U8") (pin "E15") (pinfunction "VSS_43_E15") (pintype "passive"))
      (node (ref "U8") (pin "E18") (pinfunction "VSS_44_E18") (pintype "passive"))
      (node (ref "U8") (pin "E2") (pinfunction "VSS_39_E2") (pintype "passive"))
      (node (ref "U8") (pin "E21") (pinfunction "VSS_45_E21") (pintype "passive"))
      (node (ref "U8") (pin "E24") (pinfunction "VSS_46_E24") (pintype "passive"))
      (node (ref "U8") (pin "E31") (pinfunction "VSS_47_E31") (pintype "passive"))
      (node (ref "U8") (pin "E4") (pinfunction "VSS_40_E4") (pintype "passive"))
      (node (ref "U8") (pin "E7") (pinfunction "VSS_41_E7") (pintype "passive"))
      (node (ref "U8") (pin "F15") (pinfunction "VSS_49_F15") (pintype "passive"))
      (node (ref "U8") (pin "F18") (pinfunction "VSS_50_F18") (pintype "passive"))
      (node (ref "U8") (pin "F20") (pinfunction "VSS_51_F20") (pintype "passive"))
      (node (ref "U8") (pin "F21") (pinfunction "VSS_52_F21") (pintype "passive"))
      (node (ref "U8") (pin "F8") (pinfunction "VSS_48_F8") (pintype "passive"))
      (node (ref "U8") (pin "G18") (pinfunction "VSS_55_G18") (pintype "passive"))
      (node (ref "U8") (pin "G27") (pinfunction "VSS_56_G27") (pintype "passive"))
      (node (ref "U8") (pin "G5") (pinfunction "VSS_53_G5") (pintype "passive"))
      (node (ref "U8") (pin "G9") (pinfunction "VSS_54_G9") (pintype "passive"))
      (node (ref "U8") (pin "H10") (pinfunction "VSS_59_H10") (pintype "passive"))
      (node (ref "U8") (pin "H11") (pinfunction "VSS_60_H11") (pintype "passive"))
      (node (ref "U8") (pin "H12") (pinfunction "VSS_61_H12") (pintype "passive"))
      (node (ref "U8") (pin "H13") (pinfunction "VSS_62_H13") (pintype "passive"))
      (node (ref "U8") (pin "H15") (pinfunction "VSS_63_H15") (pintype "passive"))
      (node (ref "U8") (pin "H16") (pinfunction "VSS_64_H16") (pintype "passive"))
      (node (ref "U8") (pin "H17") (pinfunction "VSS_65_H17") (pintype "passive"))
      (node (ref "U8") (pin "H18") (pinfunction "VSS_66_H18") (pintype "passive"))
      (node (ref "U8") (pin "H26") (pinfunction "VSS_67_H26") (pintype "passive"))
      (node (ref "U8") (pin "H3") (pinfunction "VSS_57_H3") (pintype "passive"))
      (node (ref "U8") (pin "H9") (pinfunction "VSS_58_H9") (pintype "passive"))
      (node (ref "U8") (pin "J10") (pinfunction "VSS_73_J10") (pintype "passive"))
      (node (ref "U8") (pin "J3") (pinfunction "VSS_68_J3") (pintype "passive"))
      (node (ref "U8") (pin "J6") (pinfunction "VSS_69_J6") (pintype "passive"))
      (node (ref "U8") (pin "J7") (pinfunction "VSS_70_J7") (pintype "passive"))
      (node (ref "U8") (pin "J8") (pinfunction "VSS_71_J8") (pintype "passive"))
      (node (ref "U8") (pin "J9") (pinfunction "VSS_72_J9") (pintype "passive"))
      (node (ref "U8") (pin "K10") (pinfunction "VSS_76_K10") (pintype "passive"))
      (node (ref "U8") (pin "K12") (pinfunction "VSS_77_K12") (pintype "passive"))
      (node (ref "U8") (pin "K14") (pinfunction "VSS_78_K14") (pintype "passive"))
      (node (ref "U8") (pin "K16") (pinfunction "VSS_79_K16") (pintype "passive"))
      (node (ref "U8") (pin "K18") (pinfunction "VSS_80_K18") (pintype "passive"))
      (node (ref "U8") (pin "K20") (pinfunction "VSS_82_K20") (pintype "passive"))
      (node (ref "U8") (pin "K22") (pinfunction "VSS_84_K22") (pintype "passive"))
      (node (ref "U8") (pin "K8") (pinfunction "VSS_74_K8") (pintype "passive"))
      (node (ref "U8") (pin "K9") (pinfunction "VSS_75_K9") (pintype "passive"))
      (node (ref "U8") (pin "L11") (pinfunction "VSS_88_L11") (pintype "passive"))
      (node (ref "U8") (pin "L12") (pinfunction "VSS_89_L12") (pintype "passive"))
      (node (ref "U8") (pin "L13") (pinfunction "VSS_90_L13") (pintype "passive"))
      (node (ref "U8") (pin "L14") (pinfunction "VSS_91_L14") (pintype "passive"))
      (node (ref "U8") (pin "L15") (pinfunction "VSS_92_L15") (pintype "passive"))
      (node (ref "U8") (pin "L16") (pinfunction "VSS_93_L16") (pintype "passive"))
      (node (ref "U8") (pin "L20") (pinfunction "VSS_96_L20") (pintype "passive"))
      (node (ref "U8") (pin "L22") (pinfunction "VSS_97_L22") (pintype "passive"))
      (node (ref "U8") (pin "L27") (pinfunction "VSS_99_L27") (pintype "passive"))
      (node (ref "U8") (pin "L3") (pinfunction "VSS_85_L3") (pintype "passive"))
      (node (ref "U8") (pin "L6") (pinfunction "VSS_86_L6") (pintype "passive"))
      (node (ref "U8") (pin "L8") (pinfunction "VSS_87_L8") (pintype "passive"))
      (node (ref "U8") (pin "M10") (pinfunction "VSS_102_M10") (pintype "passive"))
      (node (ref "U8") (pin "M16") (pinfunction "VSS_103_M16") (pintype "passive"))
      (node (ref "U8") (pin "M23") (pinfunction "VSS_104_M23") (pintype "passive"))
      (node (ref "U8") (pin "M3") (pinfunction "VSS_100_M3") (pintype "passive"))
      (node (ref "U8") (pin "M8") (pinfunction "VSS_101_M8") (pintype "passive"))
      (node (ref "U8") (pin "N13") (pinfunction "VSS_108_N13") (pintype "passive"))
      (node (ref "U8") (pin "N14") (pinfunction "VSS_109_N14") (pintype "passive"))
      (node (ref "U8") (pin "N15") (pinfunction "VSS_110_N15") (pintype "passive"))
      (node (ref "U8") (pin "N16") (pinfunction "VSS_111_N16") (pintype "passive"))
      (node (ref "U8") (pin "N17") (pinfunction "VSS_94_N17") (pintype "passive"))
      (node (ref "U8") (pin "N19") (pinfunction "VSS_83_N19") (pintype "passive"))
      (node (ref "U8") (pin "N21") (pinfunction "VSS_98_N21") (pintype "passive"))
      (node (ref "U8") (pin "N8") (pinfunction "VSS_105_N8") (pintype "passive"))
      (node (ref "U8") (pin "P10") (pinfunction "VSS_116_P10") (pintype "passive"))
      (node (ref "U8") (pin "P11") (pinfunction "VSS_106_P11") (pintype "passive"))
      (node (ref "U8") (pin "P12") (pinfunction "VSS_107_P12") (pintype "passive"))
      (node (ref "U8") (pin "P16") (pinfunction "VSS_117_P16") (pintype "passive"))
      (node (ref "U8") (pin "P19") (pinfunction "VSS_119_P19") (pintype "passive"))
      (node (ref "U8") (pin "P21") (pinfunction "VSS_121_P21") (pintype "passive"))
      (node (ref "U8") (pin "P3") (pinfunction "VSS_112_P3") (pintype "passive"))
      (node (ref "U8") (pin "P6") (pinfunction "VSS_113_P6") (pintype "passive"))
      (node (ref "U8") (pin "P7") (pinfunction "VSS_114_P7") (pintype "passive"))
      (node (ref "U8") (pin "P8") (pinfunction "VSS_115_P8") (pintype "passive"))
      (node (ref "U8") (pin "R14") (pinfunction "VSS_129_R14") (pintype "passive"))
      (node (ref "U8") (pin "R15") (pinfunction "VSS_130_R15") (pintype "passive"))
      (node (ref "U8") (pin "R16") (pinfunction "VSS_131_R16") (pintype "passive"))
      (node (ref "U8") (pin "R18") (pinfunction "VSS_165_R18") (pintype "passive"))
      (node (ref "U8") (pin "R21") (pinfunction "VSS_120_R21") (pintype "passive"))
      (node (ref "U8") (pin "R23") (pinfunction "VSS_133_R23") (pintype "passive"))
      (node (ref "U8") (pin "R3") (pinfunction "VSS_123_R3") (pintype "passive"))
      (node (ref "U8") (pin "R5") (pinfunction "VSS_124_R5") (pintype "passive"))
      (node (ref "U8") (pin "R6") (pinfunction "VSS_125_R6") (pintype "passive"))
      (node (ref "U8") (pin "T10") (pinfunction "VSS_135_T10") (pintype "passive"))
      (node (ref "U8") (pin "T16") (pinfunction "VSS_138_T16") (pintype "passive"))
      (node (ref "U8") (pin "T18") (pinfunction "VSS_168_T18") (pintype "passive"))
      (node (ref "U8") (pin "T19") (pinfunction "VSS_122_T19") (pintype "passive"))
      (node (ref "U8") (pin "T21") (pinfunction "VSS_139_T21") (pintype "passive"))
      (node (ref "U8") (pin "T8") (pinfunction "VSS_134_T8") (pintype "passive"))
      (node (ref "U8") (pin "U11") (pinfunction "VSS_126_U11") (pintype "passive"))
      (node (ref "U8") (pin "U12") (pinfunction "VSS_127_U12") (pintype "passive"))
      (node (ref "U8") (pin "U14") (pinfunction "VSS_137_U14") (pintype "passive"))
      (node (ref "U8") (pin "U15") (pinfunction "VSS_143_U15") (pintype "passive"))
      (node (ref "U8") (pin "U16") (pinfunction "VSS_144_U16") (pintype "passive"))
      (node (ref "U8") (pin "U19") (pinfunction "VSS_146_U19") (pintype "passive"))
      (node (ref "U8") (pin "U21") (pinfunction "VSS_147_U21") (pintype "passive"))
      (node (ref "U8") (pin "U22") (pinfunction "VSS_149_U22") (pintype "passive"))
      (node (ref "U8") (pin "U23") (pinfunction "AVSS_49_U23") (pintype "passive"))
      (node (ref "U8") (pin "U29") (pinfunction "VSS_150_U29") (pintype "passive"))
      (node (ref "U8") (pin "U3") (pinfunction "VSS_141_U3") (pintype "passive"))
      (node (ref "U8") (pin "U8") (pinfunction "VSS_142_U8") (pintype "passive"))
      (node (ref "U8") (pin "V10") (pinfunction "VSS_154_V10") (pintype "passive"))
      (node (ref "U8") (pin "V17") (pinfunction "VSS_148_V17") (pintype "passive"))
      (node (ref "U8") (pin "V23") (pinfunction "AVSS_50_V23") (pintype "passive"))
      (node (ref "U8") (pin "V3") (pinfunction "VSS_151_V3") (pintype "passive"))
      (node (ref "U8") (pin "V5") (pinfunction "VSS_152_V5") (pintype "passive"))
      (node (ref "U8") (pin "V8") (pinfunction "VSS_153_V8") (pintype "passive"))
      (node (ref "U8") (pin "W13") (pinfunction "VSS_128_W13") (pintype "passive"))
      (node (ref "U8") (pin "W17") (pinfunction "VSS_159_W17") (pintype "passive"))
      (node (ref "U8") (pin "W18") (pinfunction "VSS_169_W18") (pintype "passive"))
      (node (ref "U8") (pin "W19") (pinfunction "VSS_167_W19") (pintype "passive"))
      (node (ref "U8") (pin "W21") (pinfunction "VSS_81_W21") (pintype "passive"))
      (node (ref "U8") (pin "W22") (pinfunction "VSS_158_W22") (pintype "passive"))
      (node (ref "U8") (pin "W23") (pinfunction "AVSS_46_W23") (pintype "passive"))
      (node (ref "U8") (pin "W30") (pinfunction "VSS_160_W30") (pintype "passive"))
      (node (ref "U8") (pin "W8") (pinfunction "VSS_161_W8") (pintype "passive"))
      (node (ref "U8") (pin "W9") (pinfunction "VSS_162_W9") (pintype "passive"))
      (node (ref "U8") (pin "Y10") (pinfunction "VSS_15_Y10") (pintype "passive"))
      (node (ref "U8") (pin "Y11") (pinfunction "VSS_155_Y11") (pintype "passive"))
      (node (ref "U8") (pin "Y12") (pinfunction "VSS_136_Y12") (pintype "passive"))
      (node (ref "U8") (pin "Y13") (pinfunction "VSS_164_Y13") (pintype "passive"))
      (node (ref "U8") (pin "Y14") (pinfunction "VSS_156_Y14") (pintype "passive"))
      (node (ref "U8") (pin "Y15") (pinfunction "VSS_157_Y15") (pintype "passive"))
      (node (ref "U8") (pin "Y16") (pinfunction "VSS_118_Y16") (pintype "passive"))
      (node (ref "U8") (pin "Y17") (pinfunction "VSS_95_Y17") (pintype "passive"))
      (node (ref "U8") (pin "Y20") (pinfunction "VSS_170_Y20") (pintype "passive"))
      (node (ref "U8") (pin "Y23") (pinfunction "AVSS_1_Y23") (pintype "passive"))
      (node (ref "U8") (pin "Y3") (pinfunction "VSS_8_Y3") (pintype "passive"))
      (node (ref "U8") (pin "Y9") (pinfunction "VSS_166_Y9") (pintype "passive"))
    )
    (net (code "2") (name "VDD_CENTER") (class "Default")
      (node (ref "C144") (pin "2") (pinfunction "2_2") (pintype "passive"))
      (node (ref "C153") (pin "2") (pinfunction "2_2") (pintype "passive"))
      (node (ref "C154") (pin "2") (pinfunction "2_2") (pintype "passive"))
      (node (ref "C155") (pin "2") (pinfunction "2_2") (pintype "passive"))
      (node (ref "C156") (pin "2") (pinfunction "2_2") (pintype "passive"))
      (node (ref "C157") (pin "2") (pinfunction "2_2") (pintype "passive"))
      (node (ref "C158") (pin "2") (pinfunction "2_2") (pintype "passive"))
      (node (ref "C159") (pin "2") (pinfunction "2_2") (pintype "passive"))
      (node (ref "C160") (pin "2") (pinfunction "2_2") (pintype "passive"))
      (node (ref "U8") (pin "M11") (pinfunction "CENTERLOGIC_VDD_1_M11") (pintype "passive"))
      (node (ref "U8") (pin "M12") (pinfunction "CENTERLOGIC_VDD_2_M12") (pintype "passive"))
      (node (ref "U8") (pin "M13") (pinfunction "CENTERLOGIC_VDD_3_M13") (pintype "passive"))
      (node (ref "U8") (pin "M14") (pinfunction "CENTERLOGIC_VDD_4_M14") (pintype "passive"))
      (node (ref "U8") (pin "M15") (pinfunction "CENTERLOGIC_VDD_5_M15") (pintype "passive"))
      (node (ref "U8") (pin "N11") (pinfunction "CENTERLOGIC_VDD_6_N11") (pintype "passive"))
      (node (ref "U8") (pin "N12") (pinfunction "CENTERLOGIC_VDD_7_N12") (pintype "passive"))
      (node (ref "U8") (pin "P13") (pinfunction "CENTERLOGIC_VDD_8_P13") (pintype "passive"))
      (node (ref "U8") (pin "P14") (pinfunction "CENTERLOGIC_VDD_9_P14") (pintype "passive"))
      (node (ref "U8") (pin "P15") (pinfunction "CENTERLOGIC_VDD_10_P15") (pintype "passive"))
    )
    (net (code "3") (name "VDD_CPU_B") (class "Default")
      (node (ref "C141") (pin "2") (pinfunction "2_2") (pintype "passive"))
      (node (ref "C169") (pin "2") (pinfunction "2_2") (pintype "passive"))
      (node (ref "C170") (pin "2") (pinfunction "2_2") (pintype "passive"))
      (node (ref "C171") (pin "2") (pinfunction "2_2") (pintype "passive"))
      (node (ref "C172") (pin "2") (pinfunction "2_2") (pintype "passive"))
      (node (ref "C173") (pin "2") (pinfunction "2_2") (pintype "passive"))
      (node (ref "C174") (pin "2") (pinfunction "2_2") (pintype "passive"))
      (node (ref "C175") (pin "2") (pinfunction "2_2") (pintype "passive"))
      (node (ref "C176") (pin "2") (pinfunction "2_2") (pintype "passive"))
      (node (ref "C177") (pin "2") (pinfunction "2_2") (pintype "passive"))
      (node (ref "C178") (pin "2") (pinfunction "2_2") (pintype "passive"))
      (node (ref "U8") (pin "K19") (pinfunction "BIGCPU_VDD_12_K19") (pintype "passive"))
      (node (ref "U8") (pin "K21") (pinfunction "BIGCPU_VDD_13_K21") (pintype "passive"))
      (node (ref "U8") (pin "L18") (pinfunction "BIGCPU_VDD_8_L18") (pintype "passive"))
      (node (ref "U8") (pin "L19") (pinfunction "BIGCPU_VDD_1_L19") (pintype "passive"))
      (node (ref "U8") (pin "L21") (pinfunction "BIGCPU_VDD_2_L21") (pintype "passive"))
      (node (ref "U8") (pin "L23") (pinfunction "BIGCPU_VDD_11_L23") (pintype "passive"))
      (node (ref "U8") (pin "M18") (pinfunction "BIGCPU_VDD_3_M18") (pintype "passive"))
      (node (ref "U8") (pin "M19") (pinfunction "BIGCPU_VDD_4_M19") (pintype "passive"))
      (node (ref "U8") (pin "M20") (pinfunction "BIGCPU_VDD_5_M20") (pintype "passive"))
      (node (ref "U8") (pin "M21") (pinfunction "BIGCPU_VDD_6_M21") (pintype "passive"))
      (node (ref "U8") (pin "M22") (pinfunction "BIGCPU_VDD_7_M22") (pintype "passive"))
      (node (ref "U8") (pin "N20") (pinfunction "BIGCPU_VDD_10_N20") (pintype "passive"))
      (node (ref "U8") (pin "N22") (pinfunction "BIGCPU_VDD_9_N22") (pintype "passive"))
    )
    (net (code "4") (name "VDD_CPU_B_FB") (class "Default")
      (node (ref "U8") (pin "N18") (pinfunction "BIGCPU_VDD_COM_N18") (pintype "passive"))
    )
    (net (code "5") (name "VDD_CPU_L") (class "Default")
      (node (ref "C140") (pin "2") (pinfunction "2_2") (pintype "passive"))
      (node (ref "C161") (pin "2") (pinfunction "2_2") (pintype "passive"))
      (node (ref "C162") (pin "2") (pinfunction "2_2") (pintype "passive"))
      (node (ref "C163") (pin "2") (pinfunction "2_2") (pintype "passive"))
      (node (ref "C164") (pin "2") (pinfunction "2_2") (pintype "passive"))
      (node (ref "C165") (pin "2") (pinfunction "2_2") (pintype "passive"))
      (node (ref "C166") (pin "2") (pinfunction "2_2") (pintype "passive"))
      (node (ref "C167") (pin "2") (pinfunction "2_2") (pintype "passive"))
      (node (ref "C168") (pin "2") (pinfunction "2_2") (pintype "passive"))
      (node (ref "U8") (pin "P20") (pinfunction "LITCPU_VDD_1_P20") (pintype "passive"))
      (node (ref "U8") (pin "P22") (pinfunction "LITCPU_VDD_4_P22") (pintype "passive"))
      (node (ref "U8") (pin "R19") (pinfunction "LITCPU_VDD_2_R19") (pintype "passive"))
      (node (ref "U8") (pin "R20") (pinfunction "LITCPU_VDD_3_R20") (pintype "passive"))
      (node (ref "U8") (pin "R22") (pinfunction "LITCPU_VDD_7_R22") (pintype "passive"))
      (node (ref "U8") (pin "T20") (pinfunction "LITCPU_VDD_6_T20") (pintype "passive"))
      (node (ref "U8") (pin "T22") (pinfunction "LITCPU_VDD_5_T22") (pintype "passive"))
    )
    (net (code "6") (name "VDD_GPU") (class "Default")
      (node (ref "C143") (pin "2") (pinfunction "2_2") (pintype "passive"))
      (node (ref "C179") (pin "2") (pinfunction "2_2") (pintype "passive"))
      (node (ref "C180") (pin "2") (pinfunction "2_2") (pintype "passive"))
      (node (ref "C181") (pin "2") (pinfunction "2_2") (pintype "passive"))
      (node (ref "C182") (pin "2") (pinfunction "2_2") (pintype "passive"))
      (node (ref "C183") (pin "2") (pinfunction "2_2") (pintype "passive"))
      (node (ref "C184") (pin "2") (pinfunction "2_2") (pintype "passive"))
      (node (ref "C185") (pin "2") (pinfunction "2_2") (pintype "passive"))
      (node (ref "C186") (pin "2") (pinfunction "2_2") (pintype "passive"))
      (node (ref "C187") (pin "2") (pinfunction "2_2") (pintype "passive"))
      (node (ref "C188") (pin "2") (pinfunction "2_2") (pintype "passive"))
      (node (ref "C189") (pin "2") (pinfunction "2_2") (pintype "passive"))
      (node (ref "C190") (pin "2") (pinfunction "2_2") (pintype "passive"))
      (node (ref "C191") (pin "2") (pinfunction "2_2") (pintype "passive"))
      (node (ref "C192") (pin "2") (pinfunction "2_2") (pintype "passive"))
      (node (ref "C193") (pin "2") (pinfunction "2_2") (pintype "passive"))
      (node (ref "C194") (pin "2") (pinfunction "2_2") (pintype "passive"))
      (node (ref "U8") (pin "R11") (pinfunction "GPU_VDD_8_R11") (pintype "passive"))
      (node (ref "U8") (pin "R12") (pinfunction "GPU_VDD_9_R12") (pintype "passive"))
      (node (ref "U8") (pin "R13") (pinfunction "GPU_VDD_13_R13") (pintype "passive"))
      (node (ref "U8") (pin "T11") (pinfunction "GPU_VDD_10_T11") (pintype "passive"))
      (node (ref "U8") (pin "T12") (pinfunction "GPU_VDD_11_T12") (pintype "passive"))
      (node (ref "U8") (pin "T13") (pinfunction "GPU_VDD_12_T13") (pintype "passive"))
      (node (ref "U8") (pin "T14") (pinfunction "GPU_VDD_14_T14") (pintype "passive"))
      (node (ref "U8") (pin "U13") (pinfunction "GPU_VDD_7_U13") (pintype "passive"))
      (node (ref "U8") (pin "V11") (pinfunction "GPU_VDD_15_V11") (pintype "passive"))
      (node (ref "U8") (pin "V12") (pinfunction "GPU_VDD_16_V12") (pintype "passive"))
      (node (ref "U8") (pin "V13") (pinfunction "GPU_VDD_6_V13") (pintype "passive"))
      (node (ref "U8") (pin "V14") (pinfunction "GPU_VDD_5_V14") (pintype "passive"))
      (node (ref "U8") (pin "V15") (pinfunction "GPU_VDD_4_V15") (pintype "passive"))
      (node (ref "U8") (pin "V16") (pinfunction "GPU_VDD_17_V16") (pintype "passive"))
      (node (ref "U8") (pin "W10") (pinfunction "GPU_VDD_20_W10") (pintype "passive"))
      (node (ref "U8") (pin "W11") (pinfunction "GPU_VDD_1_W11") (pintype "passive"))
      (node (ref "U8") (pin "W12") (pinfunction "GPU_VDD_2_W12") (pintype "passive"))
      (node (ref "U8") (pin "W14") (pinfunction "GPU_VDD_3_W14") (pintype "passive"))
      (node (ref "U8") (pin "W15") (pinfunction "GPU_VDD_19_W15") (pintype "passive"))
      (node (ref "U8") (pin "W16") (pinfunction "GPU_VDD_18_W16") (pintype "passive"))
    )
    (net (code "7") (name "VDD_GPU_FB") (class "Default")
      (node (ref "U8") (pin "T15") (pinfunction "GPU_VDD_COM_T15") (pintype "passive"))
    )
    (net (code "8") (name "VDD_LOG") (class "Default")
      (node (ref "C142") (pin "2") (pinfunction "2_2") (pintype "passive"))
      (node (ref "C145") (pin "2") (pinfunction "2_2") (pintype "passive"))
      (node (ref "C146") (pin "2") (pinfunction "2_2") (pintype "passive"))
      (node (ref "C147") (pin "2") (pinfunction "2_2") (pintype "passive"))
      (node (ref "C148") (pin "2") (pinfunction "2_2") (pintype "passive"))
      (node (ref "C149") (pin "2") (pinfunction "2_2") (pintype "passive"))
      (node (ref "C150") (pin "2") (pinfunction "2_2") (pintype "passive"))
      (node (ref "C151") (pin "2") (pinfunction "2_2") (pintype "passive"))
      (node (ref "C152") (pin "2") (pinfunction "2_2") (pintype "passive"))
      (node (ref "U8") (pin "L17") (pinfunction "LOGIC_VDD_10_L17") (pintype "passive"))
      (node (ref "U8") (pin "M17") (pinfunction "LOGIC_VDD_9_M17") (pintype "passive"))
      (node (ref "U8") (pin "T17") (pinfunction "LOGIC_VDD_11_T17") (pintype "passive"))
      (node (ref "U8") (pin "U17") (pinfunction "LOGIC_VDD_8_U17") (pintype "passive"))
      (node (ref "U8") (pin "U18") (pinfunction "LOGIC_VDD_7_U18") (pintype "passive"))
      (node (ref "U8") (pin "U20") (pinfunction "LOGIC_VDD_12_U20") (pintype "passive"))
      (node (ref "U8") (pin "V18") (pinfunction "LOGIC_VDD_5_V18") (pintype "passive"))
      (node (ref "U8") (pin "V19") (pinfunction "LOGIC_VDD_4_V19") (pintype "passive"))
      (node (ref "U8") (pin "V20") (pinfunction "LOGIC_VDD_3_V20") (pintype "passive"))
      (node (ref "U8") (pin "V21") (pinfunction "LOGIC_VDD_2_V21") (pintype "passive"))
      (node (ref "U8") (pin "V22") (pinfunction "LOGIC_VDD_1_V22") (pintype "passive"))
      (node (ref "U8") (pin "W20") (pinfunction "LOGIC_VDD_6_W20") (pintype "passive"))
    )
  )
)
